# design.net
KiCad netlist of a schematic drawn in Altium Designer
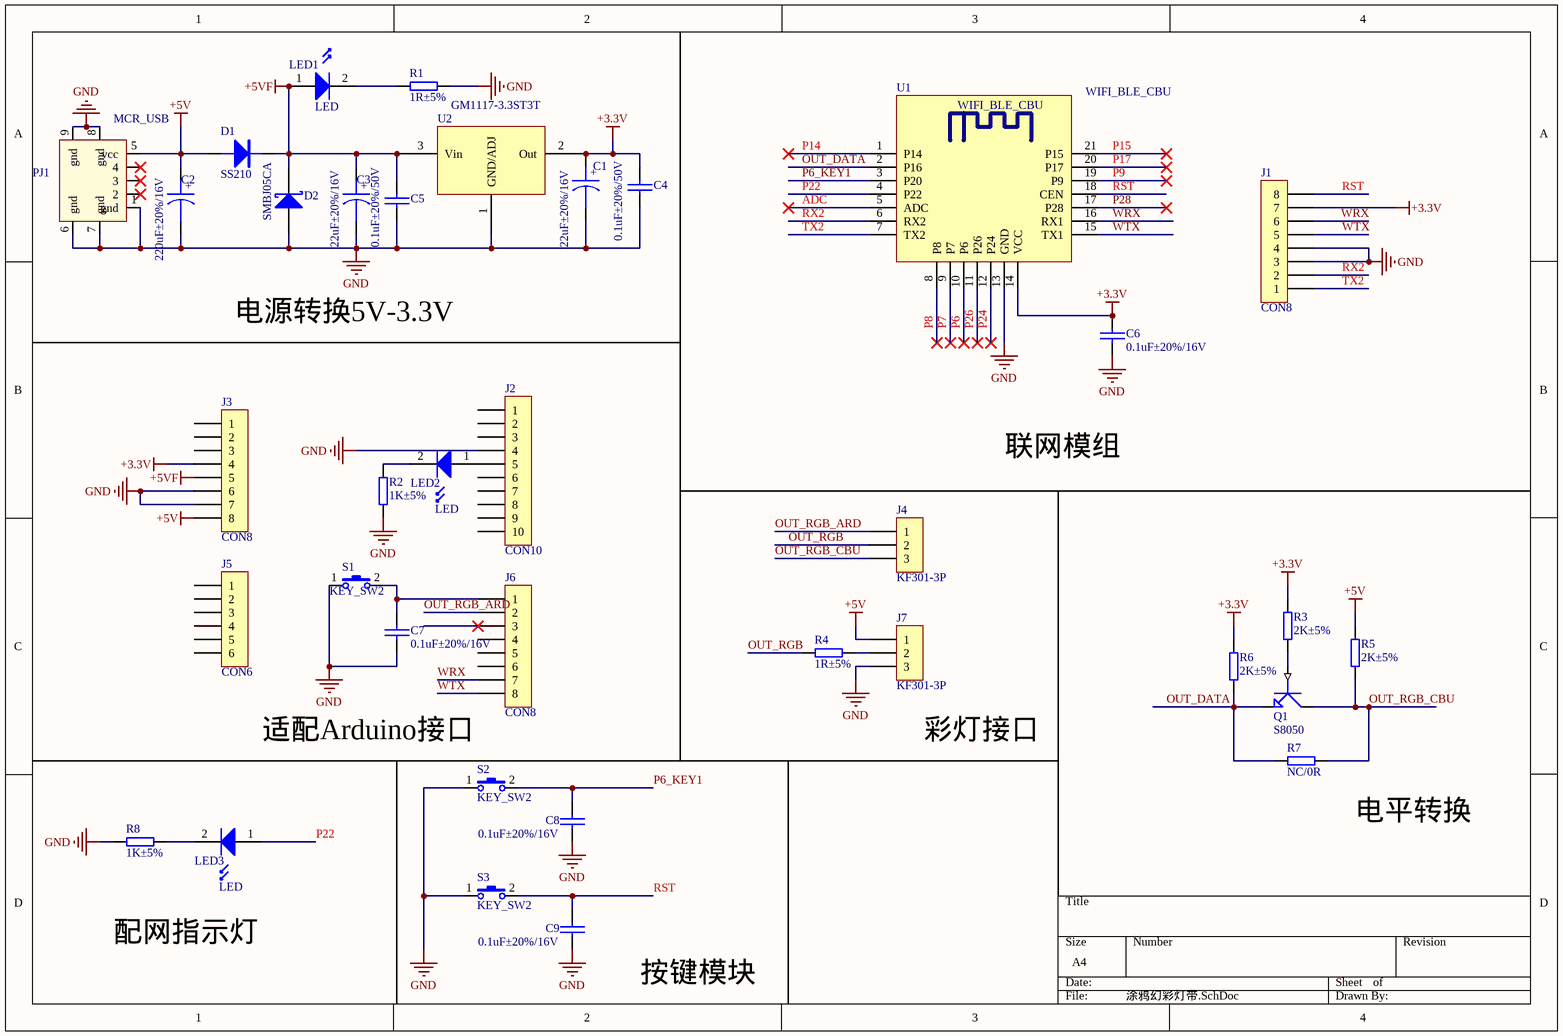
[diagram p0: 涂鸦幻彩灯带.SchDoc]

(export (version "E")
  (design (tool "Eeschema 10.0.6"))
  (components
    (comp (ref "C1")
      (value "22uF±20%/16V")
      (footprint "钽电容B3528")
      (description "Capacitor")
      (libsource (lib "*") (part "CAPACITOR POL"))
    )
    (comp (ref "C2")
      (value "220uF±20%/16V")
      (footprint "CD0.15")
      (description "Capacitor")
      (libsource (lib "*") (part "CAPACITOR POL"))
    )
    (comp (ref "C3")
      (value "22uF±20%/16V")
      (footprint "钽电容B3528")
      (description "Capacitor")
      (libsource (lib "*") (part "CAPACITOR POL"))
    )
    (comp (ref "C4")
      (value "0.1uF±20%/50V")
      (footprint "C0603")
      (description "Capacitor")
      (libsource (lib "昊华元件库sch") (part "CAP"))
    )
    (comp (ref "C5")
      (value "0.1uF±20%/50V")
      (footprint "C0603")
      (description "Capacitor")
      (libsource (lib "昊华元件库sch") (part "CAP"))
    )
    (comp (ref "C6")
      (value "0.1uF±20%/16V")
      (footprint "C0603")
      (description "Capacitor")
      (libsource (lib "昊华元件库sch") (part "CAP"))
    )
    (comp (ref "C7")
      (value "0.1uF±20%/16V")
      (footprint "C0603")
      (description "Capacitor")
      (libsource (lib "昊华元件库sch") (part "CAP"))
    )
    (comp (ref "C8")
      (value "0.1uF±20%/16V")
      (footprint "C0603")
      (description "Capacitor")
      (libsource (lib "昊华元件库sch") (part "CAP"))
    )
    (comp (ref "C9")
      (value "0.1uF±20%/16V")
      (footprint "C0603")
      (description "Capacitor")
      (libsource (lib "昊华元件库sch") (part "CAP"))
    )
    (comp (ref "D1")
      (value "SS210")
      (footprint "SMA(DO-214AC)")
      (description "Diode")
      (libsource (lib "小马元件库sch") (part "Diode1"))
    )
    (comp (ref "D2")
      (value "SMBJ05CA")
      (footprint "SMB(DO-214AA)")
      (description "Schottky Diode")
      (fields (field (name "MFR") "Toshiba"))
      (libsource (lib "Miscellaneous Devices") (part "D Schottky"))
    )
    (comp (ref "J1")
      (value "CON8")
      (footprint "HDR1X8Z")
      (description "Connector")
      (libsource (lib "小马元件库sch") (part "CON8"))
    )
    (comp (ref "J2")
      (value "CON10")
      (footprint "HDR1X10Z")
      (description "Connector")
      (libsource (lib "小马元件库sch") (part "CON10"))
    )
    (comp (ref "J3")
      (value "CON8")
      (footprint "HDR1X8Z")
      (description "Connector")
      (libsource (lib "") (part "CON8_1"))
    )
    (comp (ref "J4")
      (value "KF301-3P")
      (footprint "SIP3 - 2.54")
      (description "Connector")
      (libsource (lib "小马元件库sch") (part "CON3"))
    )
    (comp (ref "J5")
      (value "CON6")
      (footprint "HDR1X6Z")
      (description "Connector")
      (libsource (lib "小马元件库sch") (part "CON6"))
    )
    (comp (ref "J6")
      (value "CON8")
      (footprint "HDR1X8Z")
      (description "Connector")
      (libsource (lib "") (part "CON8_1"))
    )
    (comp (ref "J7")
      (value "KF301-3P")
      (footprint "SIP3 - 2.54")
      (description "Connector")
      (libsource (lib "小马元件库sch") (part "CON3"))
    )
    (comp (ref "LED1")
      (value "LED")
      (footprint "LED0805_1")
      (fields (field (name "PUBLISHER") "*"))
      (libsource (lib "小马元件库sch") (part "LED"))
    )
    (comp (ref "LED2")
      (value "LED")
      (footprint "LED0805_1")
      (fields (field (name "PUBLISHER") "*"))
      (libsource (lib "小马元件库sch") (part "LED"))
    )
    (comp (ref "LED3")
      (value "LED")
      (footprint "LED0805_1")
      (fields (field (name "PUBLISHER") "*"))
      (libsource (lib "小马元件库sch") (part "LED"))
    )
    (comp (ref "PJ1")
      (value "MCR_USB")
      (footprint "MICRO_USB-NEW-16.12.12")
      (fields (field (name "PUBLISHER") "*"))
      (libsource (lib "昊华元件库sch") (part "MCR_USB"))
    )
    (comp (ref "Q1")
      (value "S8050")
      (footprint "SOT-23-NPN")
      (description "NPN Transistor")
      (libsource (lib "小马元件库sch") (part "NPN"))
    )
    (comp (ref "R1") (value "1R±5%") (footprint "R0603") (libsource (lib "昊华元件库sch") (part "RES5")))
    (comp (ref "R2") (value "1K±5%") (footprint "R0603") (libsource (lib "昊华元件库sch") (part "RES5")))
    (comp (ref "R3") (value "2K±5%") (footprint "R0603") (libsource (lib "昊华元件库sch") (part "RES5")))
    (comp (ref "R4") (value "1R±5%") (footprint "R0603") (libsource (lib "昊华元件库sch") (part "RES5")))
    (comp (ref "R5") (value "2K±5%") (footprint "R0603") (libsource (lib "昊华元件库sch") (part "RES5")))
    (comp (ref "R6") (value "2K±5%") (footprint "R0603") (libsource (lib "昊华元件库sch") (part "RES5")))
    (comp (ref "R7") (value "NC/0R") (footprint "R0603") (libsource (lib "昊华元件库sch") (part "RES5")))
    (comp (ref "R8") (value "1K±5%") (footprint "R0603") (libsource (lib "昊华元件库sch") (part "RES5")))
    (comp (ref "S1") (value "KEY_SW2") (footprint "KEY4-SMD") (libsource (lib "小马元件库sch") (part "KEY_SW2")))
    (comp (ref "S2") (value "KEY_SW2") (footprint "KEY4-SMD") (libsource (lib "小马元件库sch") (part "KEY_SW2")))
    (comp (ref "S3") (value "KEY_SW2") (footprint "KEY4-SMD") (libsource (lib "小马元件库sch") (part "KEY_SW2")))
    (comp (ref "U1")
      (value "WIFI_BLE_CBU")
      (footprint "WIFI_BLE_CBU")
      (description "Module")
      (libsource (lib "TYModeSchlib V03") (part "WIFI_BLE_CBU"))
    )
    (comp (ref "U2") (value "GM1117-3.3ST3T") (footprint "SOT-223") (libsource (lib "mylib") (part "GM1117")))
  )
  (nets
    (net (code "1") (name "+3.3V") (class "Default")
      (node (ref "C1") (pin "1") (pinfunction "1_1") (pintype "passive"))
      (node (ref "C4") (pin "1") (pinfunction "1_1") (pintype "passive"))
      (node (ref "C6") (pin "2") (pinfunction "2_2") (pintype "passive"))
      (node (ref "J1") (pin "7") (pinfunction "7_7") (pintype "passive"))
      (node (ref "J3") (pin "4") (pinfunction "4_4") (pintype "passive"))
      (node (ref "R3") (pin "1") (pinfunction "1_1") (pintype "passive"))
      (node (ref "R6") (pin "1") (pinfunction "1_1") (pintype "passive"))
      (node (ref "U1") (pin "14") (pinfunction "VCC_14") (pintype "passive"))
      (node (ref "U2") (pin "2") (pinfunction "Out_2") (pintype "passive"))
    )
    (net (code "2") (name "+5V") (class "Default")
      (node (ref "C2") (pin "1") (pinfunction "1_1") (pintype "passive"))
      (node (ref "D1") (pin "1") (pinfunction "1_1") (pintype "passive"))
      (node (ref "J3") (pin "8") (pinfunction "8_8") (pintype "passive"))
      (node (ref "J7") (pin "1") (pinfunction "1_1") (pintype "passive"))
      (node (ref "PJ1") (pin "5") (pinfunction "vcc_5") (pintype "passive"))
      (node (ref "R5") (pin "1") (pinfunction "1_1") (pintype "passive"))
    )
    (net (code "3") (name "+5VF") (class "Default")
      (node (ref "C3") (pin "1") (pinfunction "1_1") (pintype "passive"))
      (node (ref "C5") (pin "1") (pinfunction "1_1") (pintype "passive"))
      (node (ref "D1") (pin "2") (pinfunction "2_2") (pintype "passive"))
      (node (ref "D2") (pin "2") (pinfunction "K_2") (pintype "passive"))
      (node (ref "J3") (pin "5") (pinfunction "5_5") (pintype "passive"))
      (node (ref "LED1") (pin "1") (pinfunction "1_1") (pintype "passive"))
      (node (ref "U2") (pin "3") (pinfunction "Vin_3") (pintype "passive"))
    )
    (net (code "4") (name "/ADC") (class "Default")
      (node (ref "U1") (pin "5") (pinfunction "ADC_5") (pintype "passive+no_connect"))
    )
    (net (code "5") (name "/OUT_DATA") (class "Default")
      (node (ref "Q1") (pin "1") (pinfunction "E_1") (pintype "passive"))
      (node (ref "R6") (pin "2") (pinfunction "2_2") (pintype "passive"))
      (node (ref "R7") (pin "1") (pinfunction "1_1") (pintype "passive"))
      (node (ref "U1") (pin "2") (pinfunction "P16_2") (pintype "passive"))
    )
    (net (code "6") (name "/OUT_RGB") (class "Default")
      (node (ref "J4") (pin "2") (pinfunction "2_2") (pintype "passive"))
      (node (ref "R4") (pin "1") (pinfunction "1_1") (pintype "passive"))
    )
    (net (code "7") (name "/OUT_RGB_ARD") (class "Default")
      (node (ref "J4") (pin "1") (pinfunction "1_1") (pintype "passive"))
      (node (ref "J6") (pin "2") (pinfunction "2_2") (pintype "passive"))
    )
    (net (code "8") (name "/OUT_RGB_CBU") (class "Default")
      (node (ref "J4") (pin "3") (pinfunction "3_3") (pintype "passive"))
      (node (ref "Q1") (pin "3") (pinfunction "C_3") (pintype "passive"))
      (node (ref "R5") (pin "2") (pinfunction "2_2") (pintype "passive"))
      (node (ref "R7") (pin "2") (pinfunction "2_2") (pintype "passive"))
    )
    (net (code "9") (name "/P6") (class "Default")
      (node (ref "U1") (pin "10") (pinfunction "P6_10") (pintype "passive+no_connect"))
    )
    (net (code "10") (name "/P6_KEY1") (class "Default")
      (node (ref "C8") (pin "2") (pinfunction "2_2") (pintype "passive"))
      (node (ref "S2") (pin "2") (pinfunction "2_2") (pintype "passive"))
      (node (ref "U1") (pin "3") (pinfunction "P20_3") (pintype "passive"))
    )
    (net (code "11") (name "/P7") (class "Default")
      (node (ref "U1") (pin "9") (pinfunction "P7_9") (pintype "passive+no_connect"))
    )
    (net (code "12") (name "/P8") (class "Default")
      (node (ref "U1") (pin "8") (pinfunction "P8_8") (pintype "passive+no_connect"))
    )
    (net (code "13") (name "/P9") (class "Default")
      (node (ref "U1") (pin "19") (pinfunction "P9_19") (pintype "passive+no_connect"))
    )
    (net (code "14") (name "/P14") (class "Default")
      (node (ref "U1") (pin "1") (pinfunction "P14_1") (pintype "passive+no_connect"))
    )
    (net (code "15") (name "/P15") (class "Default")
      (node (ref "U1") (pin "21") (pinfunction "P15_21") (pintype "passive+no_connect"))
    )
    (net (code "16") (name "/P17") (class "Default")
      (node (ref "U1") (pin "20") (pinfunction "P17_20") (pintype "passive+no_connect"))
    )
    (net (code "17") (name "/P22") (class "Default")
      (node (ref "LED3") (pin "1") (pinfunction "1_1") (pintype "passive"))
      (node (ref "U1") (pin "4") (pinfunction "P22_4") (pintype "passive"))
    )
    (net (code "18") (name "/P24") (class "Default")
      (node (ref "U1") (pin "12") (pinfunction "P24_12") (pintype "passive+no_connect"))
    )
    (net (code "19") (name "/P26") (class "Default")
      (node (ref "U1") (pin "11") (pinfunction "P26_11") (pintype "passive+no_connect"))
    )
    (net (code "20") (name "/P28") (class "Default")
      (node (ref "U1") (pin "17") (pinfunction "P28_17") (pintype "passive+no_connect"))
    )
    (net (code "21") (name "/RST") (class "Default")
      (node (ref "C9") (pin "2") (pinfunction "2_2") (pintype "passive"))
      (node (ref "J1") (pin "8") (pinfunction "8_8") (pintype "passive"))
      (node (ref "S3") (pin "2") (pinfunction "2_2") (pintype "passive"))
      (node (ref "U1") (pin "18") (pinfunction "CEN_18") (pintype "passive"))
    )
    (net (code "22") (name "/RX2") (class "Default")
      (node (ref "J1") (pin "2") (pinfunction "2_2") (pintype "passive"))
      (node (ref "U1") (pin "6") (pinfunction "RX2_6") (pintype "passive"))
    )
    (net (code "23") (name "/TX2") (class "Default")
      (node (ref "J1") (pin "1") (pinfunction "1_1") (pintype "passive"))
      (node (ref "U1") (pin "7") (pinfunction "TX2_7") (pintype "passive"))
    )
    (net (code "24") (name "/WRX") (class "Default")
      (node (ref "J1") (pin "6") (pinfunction "6_6") (pintype "passive"))
      (node (ref "J6") (pin "7") (pinfunction "7_7") (pintype "passive"))
      (node (ref "U1") (pin "16") (pinfunction "RX1_16") (pintype "passive"))
    )
    (net (code "25") (name "/WTX") (class "Default")
      (node (ref "J1") (pin "5") (pinfunction "5_5") (pintype "passive"))
      (node (ref "J6") (pin "8") (pinfunction "8_8") (pintype "passive"))
      (node (ref "U1") (pin "15") (pinfunction "TX1_15") (pintype "passive"))
    )
    (net (code "26") (name "GND") (class "Default")
      (node (ref "C1") (pin "2") (pinfunction "2_2") (pintype "passive"))
      (node (ref "C2") (pin "2") (pinfunction "2_2") (pintype "passive"))
      (node (ref "C3") (pin "2") (pinfunction "2_2") (pintype "passive"))
      (node (ref "C4") (pin "2") (pinfunction "2_2") (pintype "passive"))
      (node (ref "C5") (pin "2") (pinfunction "2_2") (pintype "passive"))
      (node (ref "C6") (pin "1") (pinfunction "1_1") (pintype "passive"))
      (node (ref "C7") (pin "2") (pinfunction "2_2") (pintype "passive"))
      (node (ref "C8") (pin "1") (pinfunction "1_1") (pintype "passive"))
      (node (ref "C9") (pin "1") (pinfunction "1_1") (pintype "passive"))
      (node (ref "D2") (pin "1") (pinfunction "A_1") (pintype "passive"))
      (node (ref "J1") (pin "3") (pinfunction "3_3") (pintype "passive"))
      (node (ref "J1") (pin "4") (pinfunction "4_4") (pintype "passive"))
      (node (ref "J2") (pin "4") (pinfunction "4_4") (pintype "passive"))
      (node (ref "J3") (pin "6") (pinfunction "6_6") (pintype "passive"))
      (node (ref "J3") (pin "7") (pinfunction "7_7") (pintype "passive"))
      (node (ref "J7") (pin "3") (pinfunction "3_3") (pintype "passive"))
      (node (ref "PJ1") (pin "1") (pinfunction "gnd_1") (pintype "passive"))
      (node (ref "PJ1") (pin "6") (pinfunction "gnd_6") (pintype "passive"))
      (node (ref "PJ1") (pin "7") (pinfunction "gnd_7") (pintype "passive"))
      (node (ref "PJ1") (pin "8") (pinfunction "gnd_8") (pintype "passive"))
      (node (ref "PJ1") (pin "9") (pinfunction "gnd_9") (pintype "passive"))
      (node (ref "R1") (pin "2") (pinfunction "2_2") (pintype "passive"))
      (node (ref "R2") (pin "1") (pinfunction "1_1") (pintype "passive"))
      (node (ref "R8") (pin "2") (pinfunction "2_2") (pintype "passive"))
      (node (ref "S1") (pin "1") (pinfunction "1_1") (pintype "passive"))
      (node (ref "S2") (pin "1") (pinfunction "1_1") (pintype "passive"))
      (node (ref "S3") (pin "1") (pinfunction "1_1") (pintype "passive"))
      (node (ref "U1") (pin "13") (pinfunction "GND_13") (pintype "passive"))
      (node (ref "U2") (pin "1") (pinfunction "GND/ADJ_1") (pintype "passive"))
    )
    (net (code "27") (name "Net-(C7-Pad1)") (class "Default")
      (node (ref "C7") (pin "1") (pinfunction "1_1") (pintype "passive"))
      (node (ref "J6") (pin "1") (pinfunction "1_1") (pintype "passive"))
      (node (ref "S1") (pin "2") (pinfunction "2_2") (pintype "passive"))
    )
    (net (code "28") (name "Net-(J2-Pad5)") (class "Default")
      (node (ref "J2") (pin "5") (pinfunction "5_5") (pintype "passive"))
      (node (ref "LED2") (pin "1") (pinfunction "1_1") (pintype "passive"))
    )
    (net (code "29") (name "Net-(J7-Pad2)") (class "Default")
      (node (ref "J7") (pin "2") (pinfunction "2_2") (pintype "passive"))
      (node (ref "R4") (pin "2") (pinfunction "2_2") (pintype "passive"))
    )
    (net (code "30") (name "Net-(LED1-Pad2)") (class "Default")
      (node (ref "LED1") (pin "2") (pinfunction "2_2") (pintype "passive"))
      (node (ref "R1") (pin "1") (pinfunction "1_1") (pintype "passive"))
    )
    (net (code "31") (name "Net-(LED2-Pad2)") (class "Default")
      (node (ref "LED2") (pin "2") (pinfunction "2_2") (pintype "passive"))
      (node (ref "R2") (pin "2") (pinfunction "2_2") (pintype "passive"))
    )
    (net (code "32") (name "Net-(LED3-Pad2)") (class "Default")
      (node (ref "LED3") (pin "2") (pinfunction "2_2") (pintype "passive"))
      (node (ref "R8") (pin "1") (pinfunction "1_1") (pintype "passive"))
    )
    (net (code "33") (name "Net-(Q1-B)") (class "Default")
      (node (ref "Q1") (pin "2") (pinfunction "B_2") (pintype "input"))
      (node (ref "R3") (pin "2") (pinfunction "2_2") (pintype "passive"))
    )
    (net (code "34") (name "unconnected-(J2-Pad1)") (class "Default")
      (node (ref "J2") (pin "1") (pinfunction "1_1") (pintype "passive"))
    )
    (net (code "35") (name "unconnected-(J2-Pad2)") (class "Default")
      (node (ref "J2") (pin "2") (pinfunction "2_2") (pintype "passive"))
    )
    (net (code "36") (name "unconnected-(J2-Pad3)") (class "Default")
      (node (ref "J2") (pin "3") (pinfunction "3_3") (pintype "passive"))
    )
    (net (code "37") (name "unconnected-(J2-Pad6)") (class "Default")
      (node (ref "J2") (pin "6") (pinfunction "6_6") (pintype "passive"))
    )
    (net (code "38") (name "unconnected-(J2-Pad7)") (class "Default")
      (node (ref "J2") (pin "7") (pinfunction "7_7") (pintype "passive"))
    )
    (net (code "39") (name "unconnected-(J2-Pad8)") (class "Default")
      (node (ref "J2") (pin "8") (pinfunction "8_8") (pintype "passive"))
    )
    (net (code "40") (name "unconnected-(J2-Pad9)") (class "Default")
      (node (ref "J2") (pin "9") (pinfunction "9_9") (pintype "passive"))
    )
    (net (code "41") (name "unconnected-(J2-Pad10)") (class "Default")
      (node (ref "J2") (pin "10") (pinfunction "10_10") (pintype "passive"))
    )
    (net (code "42") (name "unconnected-(J3-Pad1)") (class "Default")
      (node (ref "J3") (pin "1") (pinfunction "1_1") (pintype "passive"))
    )
    (net (code "43") (name "unconnected-(J3-Pad2)") (class "Default")
      (node (ref "J3") (pin "2") (pinfunction "2_2") (pintype "passive"))
    )
    (net (code "44") (name "unconnected-(J3-Pad3)") (class "Default")
      (node (ref "J3") (pin "3") (pinfunction "3_3") (pintype "passive"))
    )
    (net (code "45") (name "unconnected-(J5-Pad1)") (class "Default")
      (node (ref "J5") (pin "1") (pinfunction "1_1") (pintype "passive"))
    )
    (net (code "46") (name "unconnected-(J5-Pad2)") (class "Default")
      (node (ref "J5") (pin "2") (pinfunction "2_2") (pintype "passive"))
    )
    (net (code "47") (name "unconnected-(J5-Pad3)") (class "Default")
      (node (ref "J5") (pin "3") (pinfunction "3_3") (pintype "passive"))
    )
    (net (code "48") (name "unconnected-(J5-Pad4)") (class "Default")
      (node (ref "J5") (pin "4") (pinfunction "4_4") (pintype "passive"))
    )
    (net (code "49") (name "unconnected-(J5-Pad5)") (class "Default")
      (node (ref "J5") (pin "5") (pinfunction "5_5") (pintype "passive"))
    )
    (net (code "50") (name "unconnected-(J5-Pad6)") (class "Default")
      (node (ref "J5") (pin "6") (pinfunction "6_6") (pintype "passive"))
    )
    (net (code "51") (name "unconnected-(J6-Pad3)") (class "Default")
      (node (ref "J6") (pin "3") (pinfunction "3_3") (pintype "passive+no_connect"))
    )
    (net (code "52") (name "unconnected-(J6-Pad4)") (class "Default")
      (node (ref "J6") (pin "4") (pinfunction "4_4") (pintype "passive"))
    )
    (net (code "53") (name "unconnected-(J6-Pad5)") (class "Default")
      (node (ref "J6") (pin "5") (pinfunction "5_5") (pintype "passive"))
    )
    (net (code "54") (name "unconnected-(J6-Pad6)") (class "Default")
      (node (ref "J6") (pin "6") (pinfunction "6_6") (pintype "passive"))
    )
    (net (code "55") (name "unconnected-(PJ1-Pad2)") (class "Default")
      (node (ref "PJ1") (pin "2") (pinfunction "2_2") (pintype "passive+no_connect"))
    )
    (net (code "56") (name "unconnected-(PJ1-Pad3)") (class "Default")
      (node (ref "PJ1") (pin "3") (pinfunction "3_3") (pintype "passive+no_connect"))
    )
    (net (code "57") (name "unconnected-(PJ1-Pad4)") (class "Default")
      (node (ref "PJ1") (pin "4") (pinfunction "4_4") (pintype "passive+no_connect"))
    )
  )
)
